# VOC_and_eCO2_Gas_Sensor_SGP30_v1_0.net
KiCad netlist of a schematic drawn in EAGLE
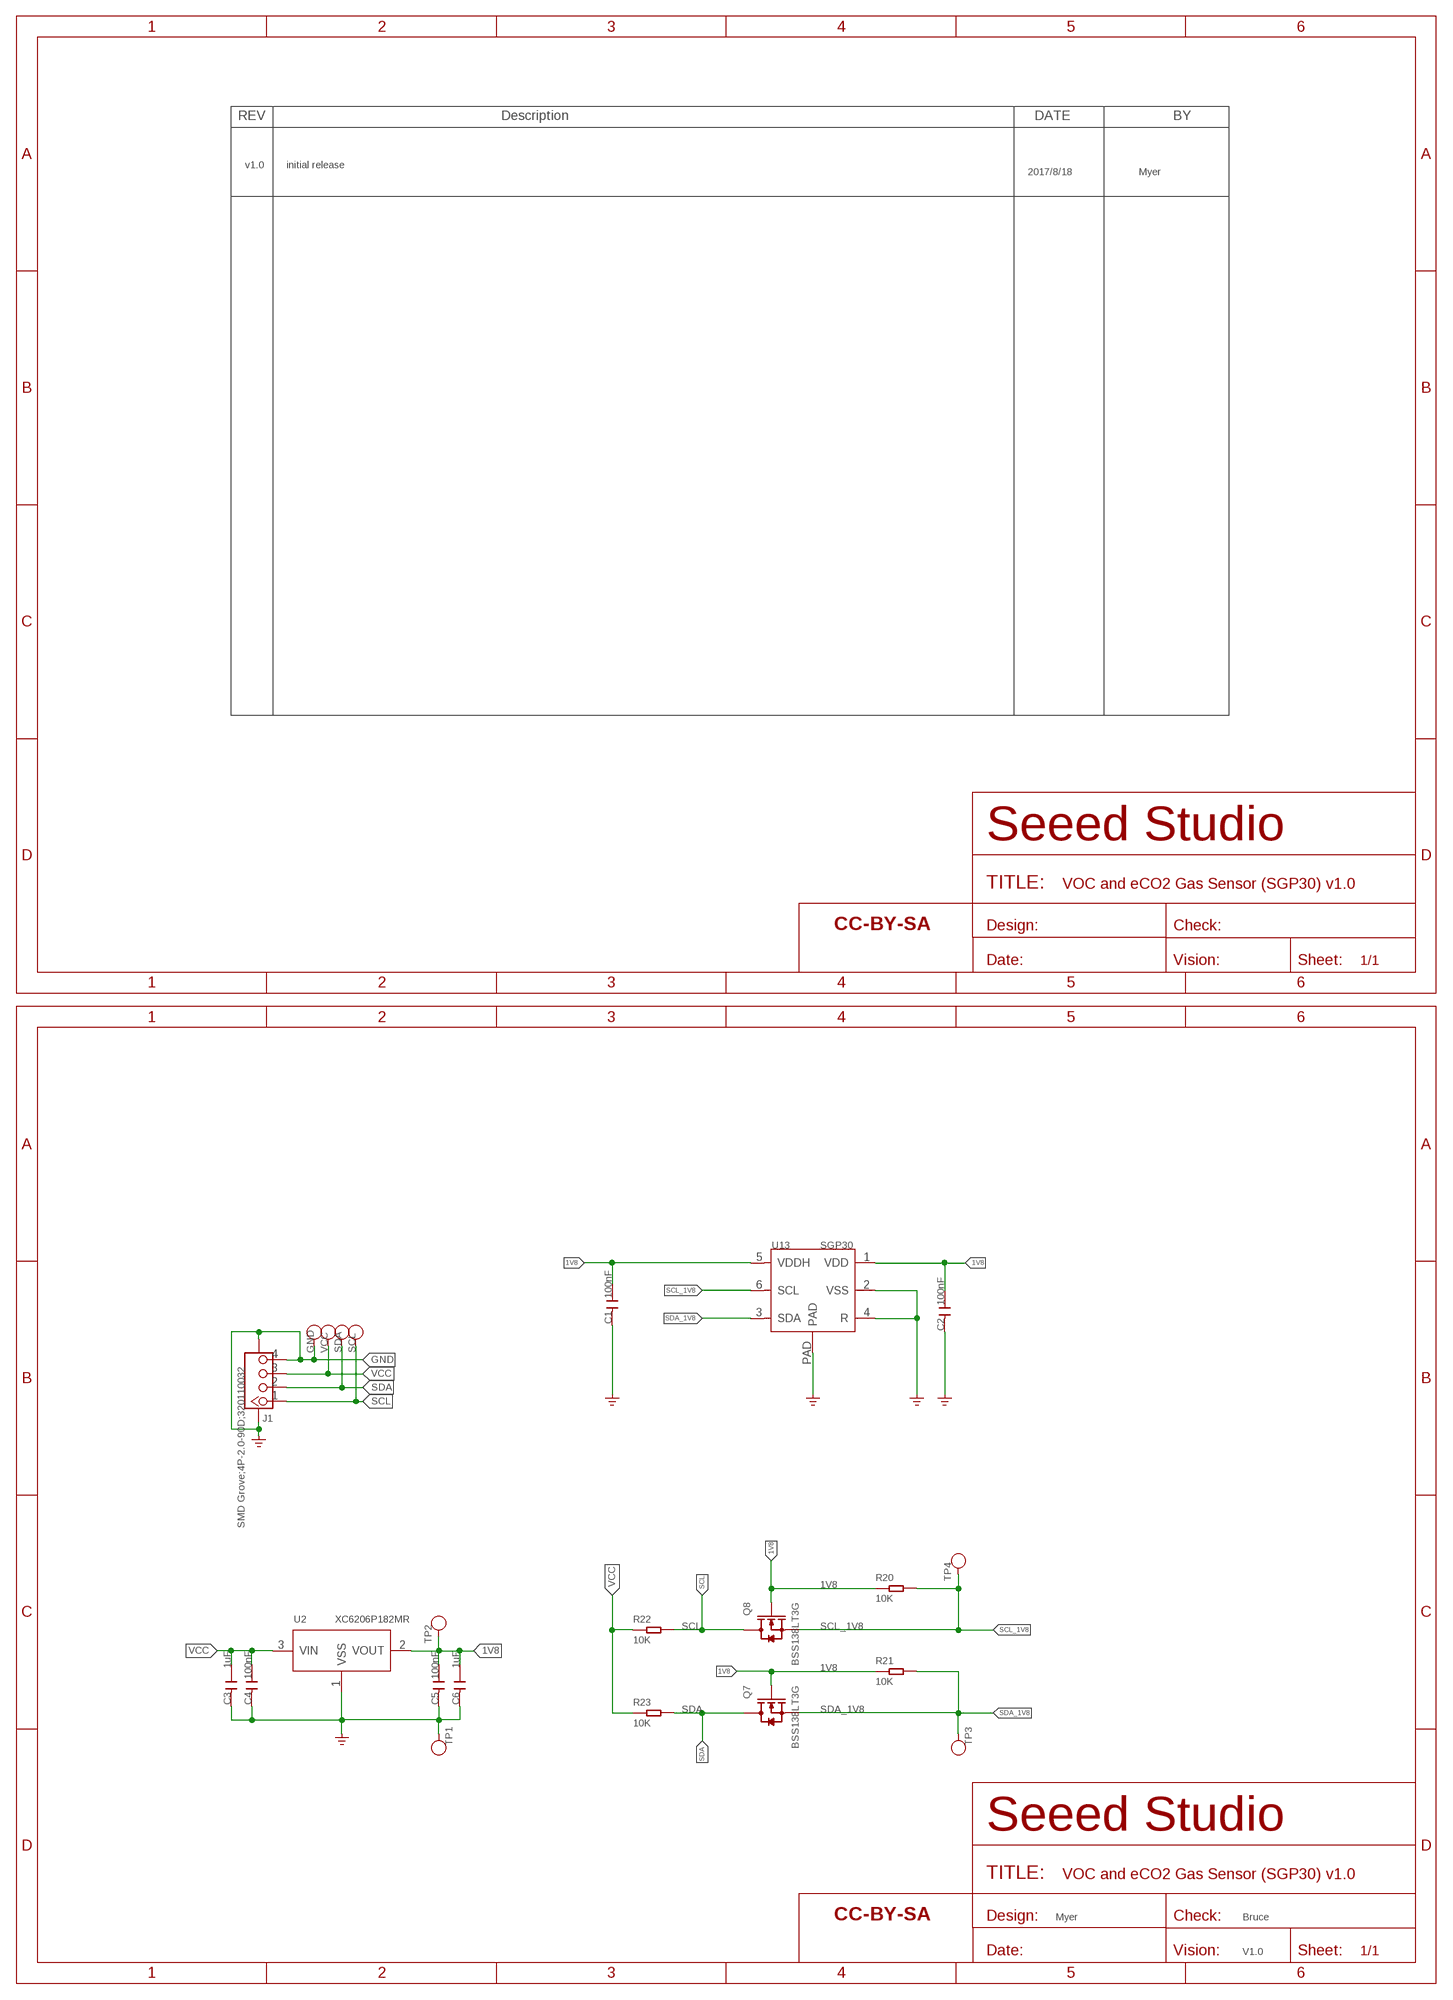
[diagram p0: schematic, sheet 1]

(export (version "E")
  (design (tool "Eeschema 10.0.6"))
  (components
    (comp (ref "C1")
      (value "100nF")
      (footprint "eagle-import:C0603")
      (libsource (lib "eagle-import") (part "CAP-0603"))
    )
    (comp (ref "C2")
      (value "100nF")
      (footprint "eagle-import:C0603")
      (libsource (lib "eagle-import") (part "CAP-0603"))
    )
    (comp (ref "C3")
      (value "1uF")
      (footprint "eagle-import:C0603")
      (libsource (lib "eagle-import") (part "CAP-0603"))
    )
    (comp (ref "C4")
      (value "100nF")
      (footprint "eagle-import:C0603")
      (libsource (lib "eagle-import") (part "CAP-0603"))
    )
    (comp (ref "C5")
      (value "100nF")
      (footprint "eagle-import:C0603")
      (libsource (lib "eagle-import") (part "CAP-0603"))
    )
    (comp (ref "C6")
      (value "1uF")
      (footprint "eagle-import:C0603")
      (libsource (lib "eagle-import") (part "CAP-0603"))
    )
    (comp (ref "FR1")
      (value "SEEEDSTUDIO-OPEN-SCH-FRAME")
      (footprint "eagle-import:SEEEDSTUDIO-PCB-FRAME")
      (libsource (lib "eagle-import") (part "SEEEDSTUDIO-OPEN-SCH-FRAME"))
    )
    (comp (ref "FR2")
      (value "SEEEDSTUDIO-OPEN-SCH-FRAME")
      (footprint "eagle-import:SEEEDSTUDIO-PCB-FRAME")
      (libsource (lib "eagle-import") (part "SEEEDSTUDIO-OPEN-SCH-FRAME"))
    )
    (comp (ref "GND")
      (value "TEST-POINT'4545'")
      (footprint "eagle-import:TP-D45MIL")
      (fields (field (name "PARTNO") "DNP"))
      (libsource (lib "eagle-import") (part "TEST-POINT'4545'"))
    )
    (comp (ref "J1")
      (value "SMD Grove;4P-2.0-90D;320110032")
      (footprint "eagle-import:HW4-SMD-2.0-90D")
      (libsource (lib "eagle-import") (part "GROVE-CONNECTOR-SMD'90D'"))
    )
    (comp (ref "Q7")
      (value "BSS138LT3G")
      (footprint "eagle-import:SOT-23")
      (libsource (lib "eagle-import") (part "MOSFET-N'SOT23'"))
    )
    (comp (ref "Q8")
      (value "BSS138LT3G")
      (footprint "eagle-import:SOT-23")
      (libsource (lib "eagle-import") (part "MOSFET-N'SOT23'"))
    )
    (comp (ref "R20")
      (value "10K")
      (footprint "eagle-import:R0603")
      (libsource (lib "eagle-import") (part "RES-0603"))
    )
    (comp (ref "R21")
      (value "10K")
      (footprint "eagle-import:R0603")
      (libsource (lib "eagle-import") (part "RES-0603"))
    )
    (comp (ref "R22")
      (value "10K")
      (footprint "eagle-import:R0603")
      (libsource (lib "eagle-import") (part "RES-0603"))
    )
    (comp (ref "R23")
      (value "10K")
      (footprint "eagle-import:R0603")
      (libsource (lib "eagle-import") (part "RES-0603"))
    )
    (comp (ref "SCL")
      (value "TEST-POINT'4545'")
      (footprint "eagle-import:TP-D45MIL")
      (fields (field (name "PARTNO") "DNP"))
      (libsource (lib "eagle-import") (part "TEST-POINT'4545'"))
    )
    (comp (ref "SDA")
      (value "TEST-POINT'4545'")
      (footprint "eagle-import:TP-D45MIL")
      (fields (field (name "PARTNO") "DNP"))
      (libsource (lib "eagle-import") (part "TEST-POINT'4545'"))
    )
    (comp (ref "TP1")
      (value "TEST-POINT'4545'")
      (footprint "eagle-import:TP-D45MIL")
      (fields (field (name "PARTNO") "DNP"))
      (libsource (lib "eagle-import") (part "TEST-POINT'4545'"))
    )
    (comp (ref "TP2")
      (value "TEST-POINT'4545'")
      (footprint "eagle-import:TP-D45MIL")
      (fields (field (name "PARTNO") "DNP"))
      (libsource (lib "eagle-import") (part "TEST-POINT'4545'"))
    )
    (comp (ref "TP3")
      (value "TEST-POINT'4545'")
      (footprint "eagle-import:TP-D45MIL")
      (fields (field (name "PARTNO") "DNP"))
      (libsource (lib "eagle-import") (part "TEST-POINT'4545'"))
    )
    (comp (ref "TP4")
      (value "TEST-POINT'4545'")
      (footprint "eagle-import:TP-D45MIL")
      (fields (field (name "PARTNO") "DNP"))
      (libsource (lib "eagle-import") (part "TEST-POINT'4545'"))
    )
    (comp (ref "U2")
      (value "XC6206P182MR")
      (footprint "eagle-import:SOT-23")
      (libsource (lib "eagle-import") (part "PMIC-XC6206PMR"))
    )
    (comp (ref "U13")
      (value "SGP30")
      (footprint "eagle-import:DFN6-0.8-2.45X2.45X0.9MM")
      (libsource (lib "eagle-import") (part "SENSOR-GAS-SGP30"))
    )
    (comp (ref "VCC")
      (value "TEST-POINT'4545'")
      (footprint "eagle-import:TP-D45MIL")
      (fields (field (name "PARTNO") "DNP"))
      (libsource (lib "eagle-import") (part "TEST-POINT'4545'"))
    )
  )
  (nets
    (net (code "1") (name "1V8") (class "Default")
      (node (ref "C1") (pin "1") (pinfunction "1_1") (pintype "passive"))
      (node (ref "C2") (pin "1") (pinfunction "1_1") (pintype "passive"))
      (node (ref "C5") (pin "1") (pinfunction "1_1") (pintype "passive"))
      (node (ref "C6") (pin "1") (pinfunction "1_1") (pintype "passive"))
      (node (ref "Q7") (pin "1") (pinfunction "G_1") (pintype "passive"))
      (node (ref "Q8") (pin "1") (pinfunction "G_1") (pintype "passive"))
      (node (ref "R20") (pin "1") (pinfunction "1_1") (pintype "passive"))
      (node (ref "R21") (pin "1") (pinfunction "1_1") (pintype "passive"))
      (node (ref "TP2") (pin "T") (pinfunction "T_T") (pintype "bidirectional"))
      (node (ref "U13") (pin "1") (pinfunction "VDD_1") (pintype "bidirectional"))
      (node (ref "U13") (pin "5") (pinfunction "VDDH_5") (pintype "bidirectional"))
      (node (ref "U2") (pin "2") (pinfunction "VOUT_2") (pintype "bidirectional"))
    )
    (net (code "2") (name "GND") (class "Default")
      (node (ref "C1") (pin "2") (pinfunction "2_2") (pintype "passive"))
      (node (ref "C2") (pin "2") (pinfunction "2_2") (pintype "passive"))
      (node (ref "C3") (pin "2") (pinfunction "2_2") (pintype "passive"))
      (node (ref "C4") (pin "2") (pinfunction "2_2") (pintype "passive"))
      (node (ref "C5") (pin "2") (pinfunction "2_2") (pintype "passive"))
      (node (ref "C6") (pin "2") (pinfunction "2_2") (pintype "passive"))
      (node (ref "GND") (pin "T") (pinfunction "T_T") (pintype "bidirectional"))
      (node (ref "J1") (pin "4") (pinfunction "4_4") (pintype "bidirectional"))
      (node (ref "J1") (pin "SS1") (pinfunction "SS1_SS1") (pintype "bidirectional"))
      (node (ref "J1") (pin "SS2") (pinfunction "SS2_SS2") (pintype "bidirectional"))
      (node (ref "TP1") (pin "T") (pinfunction "T_T") (pintype "bidirectional"))
      (node (ref "U13") (pin "2") (pinfunction "VSS_2") (pintype "bidirectional"))
      (node (ref "U13") (pin "4") (pinfunction "R_4") (pintype "bidirectional"))
      (node (ref "U13") (pin "PAD") (pinfunction "PAD_PAD") (pintype "bidirectional"))
      (node (ref "U2") (pin "1") (pinfunction "VSS_1") (pintype "bidirectional"))
    )
    (net (code "3") (name "SCL") (class "Default")
      (node (ref "J1") (pin "1") (pinfunction "1_1") (pintype "bidirectional"))
      (node (ref "Q8") (pin "3") (pinfunction "D_3") (pintype "passive"))
      (node (ref "R22") (pin "2") (pinfunction "2_2") (pintype "passive"))
      (node (ref "SCL") (pin "T") (pinfunction "T_T") (pintype "bidirectional"))
    )
    (net (code "4") (name "SCL_1V8") (class "Default")
      (node (ref "Q8") (pin "2") (pinfunction "S_2") (pintype "passive"))
      (node (ref "R20") (pin "2") (pinfunction "2_2") (pintype "passive"))
      (node (ref "TP4") (pin "T") (pinfunction "T_T") (pintype "bidirectional"))
      (node (ref "U13") (pin "6") (pinfunction "SCL_6") (pintype "bidirectional"))
    )
    (net (code "5") (name "SDA") (class "Default")
      (node (ref "J1") (pin "2") (pinfunction "2_2") (pintype "bidirectional"))
      (node (ref "Q7") (pin "3") (pinfunction "D_3") (pintype "passive"))
      (node (ref "R23") (pin "2") (pinfunction "2_2") (pintype "passive"))
      (node (ref "SDA") (pin "T") (pinfunction "T_T") (pintype "bidirectional"))
    )
    (net (code "6") (name "SDA_1V8") (class "Default")
      (node (ref "Q7") (pin "2") (pinfunction "S_2") (pintype "passive"))
      (node (ref "R21") (pin "2") (pinfunction "2_2") (pintype "passive"))
      (node (ref "TP3") (pin "T") (pinfunction "T_T") (pintype "bidirectional"))
      (node (ref "U13") (pin "3") (pinfunction "SDA_3") (pintype "bidirectional"))
    )
    (net (code "7") (name "VCC") (class "Default")
      (node (ref "C3") (pin "1") (pinfunction "1_1") (pintype "passive"))
      (node (ref "C4") (pin "1") (pinfunction "1_1") (pintype "passive"))
      (node (ref "J1") (pin "3") (pinfunction "3_3") (pintype "bidirectional"))
      (node (ref "R22") (pin "1") (pinfunction "1_1") (pintype "passive"))
      (node (ref "R23") (pin "1") (pinfunction "1_1") (pintype "passive"))
      (node (ref "U2") (pin "3") (pinfunction "VIN_3") (pintype "bidirectional"))
      (node (ref "VCC") (pin "T") (pinfunction "T_T") (pintype "bidirectional"))
    )
  )
)
